# 68000.net
KiCad netlist of a schematic drawn in EAGLE
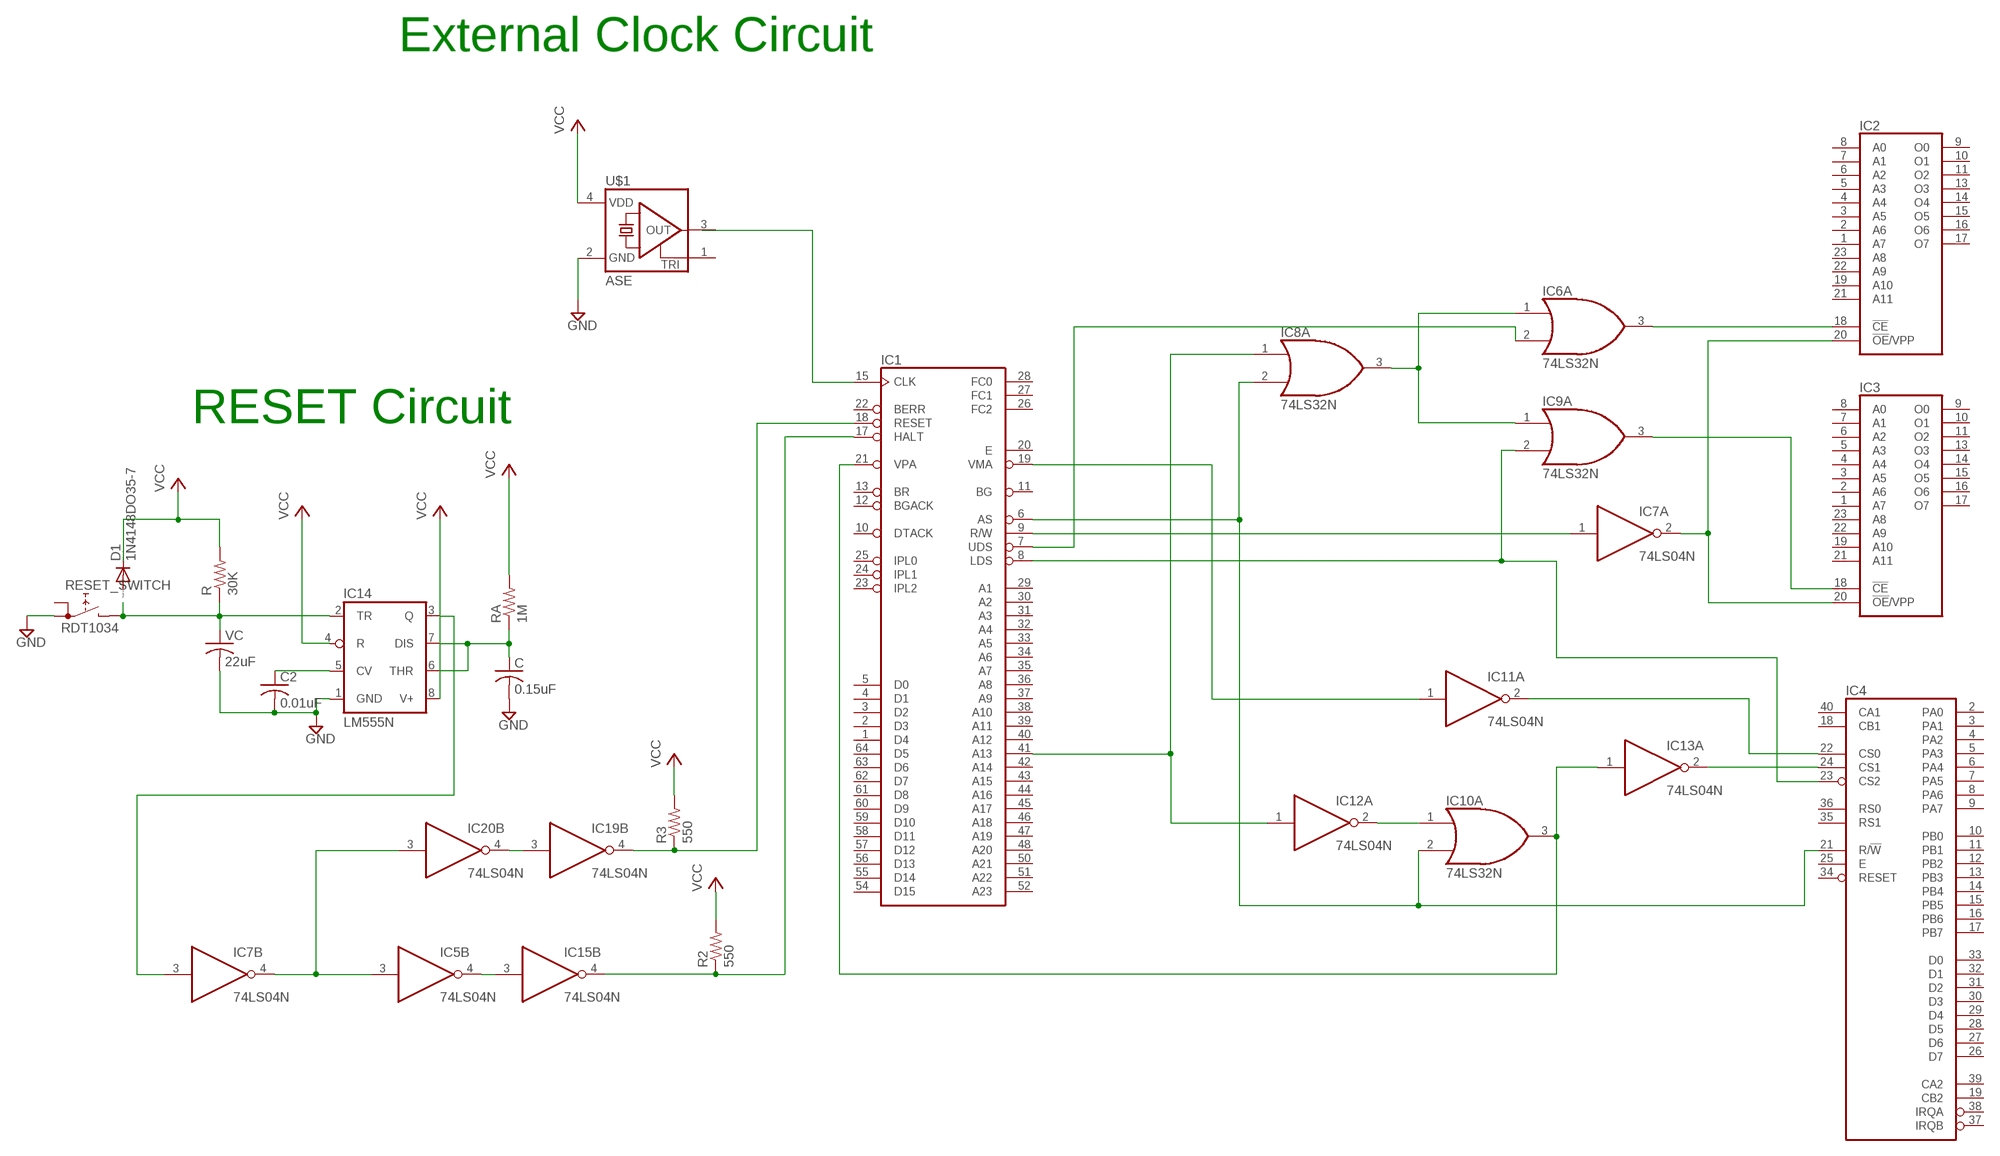
[diagram p0: schematic, sheet 1]

(export (version "E")
  (design (tool "Eeschema 10.0.6"))
  (components
    (comp (ref "C")
      (value "0.15uF")
      (footprint "eagle-import:C025-024X044")
      (libsource (lib "eagle-import") (part "C-US025-024X044"))
    )
    (comp (ref "C2")
      (value "0.01uF")
      (footprint "eagle-import:C025-024X044")
      (libsource (lib "eagle-import") (part "C-US025-024X044"))
    )
    (comp (ref "D1")
      (value "1N4148DO35-7")
      (footprint "eagle-import:DO35-7")
      (libsource (lib "eagle-import") (part "1N4148DO35-7"))
    )
    (comp (ref "IC1")
      (value "MC68000P")
      (footprint "eagle-import:DIL64")
      (libsource (lib "eagle-import") (part "MC68000P"))
    )
    (comp (ref "IC2")
      (value "2732")
      (footprint "eagle-import:DIL24")
      (libsource (lib "eagle-import") (part "2732"))
    )
    (comp (ref "IC3")
      (value "2732")
      (footprint "eagle-import:DIL24")
      (libsource (lib "eagle-import") (part "2732"))
    )
    (comp (ref "IC4")
      (value "6821")
      (footprint "eagle-import:DIL40")
      (fields (field (name "MF") "NTE ELECTRONICS") (field (name "MPN") "NTE6821"))
      (libsource (lib "eagle-import") (part "6821"))
    )
    (comp (ref "IC5")
      (value "74LS04N")
      (footprint "eagle-import:DIL14")
      (libsource (lib "eagle-import") (part "7404NLS"))
    )
    (comp (ref "IC6")
      (value "74LS32N")
      (footprint "eagle-import:DIL14")
      (libsource (lib "eagle-import") (part "7432NLS"))
    )
    (comp (ref "IC7")
      (value "74LS04N")
      (footprint "eagle-import:DIL14")
      (libsource (lib "eagle-import") (part "7404NLS"))
    )
    (comp (ref "IC8")
      (value "74LS32N")
      (footprint "eagle-import:DIL14")
      (libsource (lib "eagle-import") (part "7432NLS"))
    )
    (comp (ref "IC9")
      (value "74LS32N")
      (footprint "eagle-import:DIL14")
      (libsource (lib "eagle-import") (part "7432NLS"))
    )
    (comp (ref "IC10")
      (value "74LS32N")
      (footprint "eagle-import:DIL14")
      (libsource (lib "eagle-import") (part "7432NLS"))
    )
    (comp (ref "IC11")
      (value "74LS04N")
      (footprint "eagle-import:DIL14")
      (libsource (lib "eagle-import") (part "7404NLS"))
    )
    (comp (ref "IC12")
      (value "74LS04N")
      (footprint "eagle-import:DIL14")
      (libsource (lib "eagle-import") (part "7404NLS"))
    )
    (comp (ref "IC13")
      (value "74LS04N")
      (footprint "eagle-import:DIL14")
      (libsource (lib "eagle-import") (part "7404NLS"))
    )
    (comp (ref "IC14")
      (value "LM555N")
      (footprint "eagle-import:DIL08")
      (libsource (lib "eagle-import") (part "555NLM"))
    )
    (comp (ref "IC15")
      (value "74LS04N")
      (footprint "eagle-import:DIL14")
      (libsource (lib "eagle-import") (part "7404NLS"))
    )
    (comp (ref "IC19")
      (value "74LS04N")
      (footprint "eagle-import:DIL14")
      (libsource (lib "eagle-import") (part "7404NLS"))
    )
    (comp (ref "IC20")
      (value "74LS04N")
      (footprint "eagle-import:DIL14")
      (libsource (lib "eagle-import") (part "7404NLS"))
    )
    (comp (ref "R")
      (value "30K")
      (footprint "eagle-import:0204V")
      (libsource (lib "eagle-import") (part "R-US_0204/2V"))
    )
    (comp (ref "R2")
      (value "550")
      (footprint "eagle-import:0204V")
      (libsource (lib "eagle-import") (part "R-US_0204/2V"))
    )
    (comp (ref "R3")
      (value "550")
      (footprint "eagle-import:0204V")
      (libsource (lib "eagle-import") (part "R-US_0204/2V"))
    )
    (comp (ref "RA")
      (value "1M")
      (footprint "eagle-import:0204V")
      (libsource (lib "eagle-import") (part "R-US_0204/2V"))
    )
    (comp (ref "RESET_SWITCH")
      (value "RDT1034")
      (footprint "eagle-import:RDT1034")
      (libsource (lib "eagle-import") (part "RDT1034"))
    )
    (comp (ref "U$1")
      (value "ASE")
      (footprint "eagle-import:ASE")
      (libsource (lib "eagle-import") (part "ASE"))
    )
    (comp (ref "VC")
      (value "22uF")
      (footprint "eagle-import:C025-024X044")
      (libsource (lib "eagle-import") (part "C-US025-024X044"))
    )
  )
  (nets
    (net (code "1") (name "GND") (class "Default")
      (node (ref "C") (pin "2") (pinfunction "2_2") (pintype "passive"))
      (node (ref "C2") (pin "2") (pinfunction "2_2") (pintype "passive"))
      (node (ref "IC14") (pin "1") (pinfunction "GND_1") (pintype "power_in"))
      (node (ref "RESET_SWITCH") (pin "A1") (pinfunction "A1_A1") (pintype "passive"))
      (node (ref "U$1") (pin "2") (pinfunction "GND_2") (pintype "power_in"))
      (node (ref "VC") (pin "2") (pinfunction "2_2") (pintype "passive"))
    )
    (net (code "2") (name "Net-(IC1A-LDS)") (class "Default")
      (node (ref "IC1") (pin "8") (pinfunction "LDS_8") (pintype "output"))
      (node (ref "IC4") (pin "23") (pinfunction "CS2_23") (pintype "input"))
      (node (ref "IC9") (pin "2") (pinfunction "I1_2") (pintype "input"))
    )
    (net (code "3") (name "Net-(IC1A-R{slash}W)") (class "Default")
      (node (ref "IC1") (pin "9") (pinfunction "R/W_9") (pintype "output"))
      (node (ref "IC7") (pin "1") (pinfunction "I_1") (pintype "input"))
    )
    (net (code "4") (name "Net-(IC1A-UDS)") (class "Default")
      (node (ref "IC1") (pin "7") (pinfunction "UDS_7") (pintype "output"))
      (node (ref "IC6") (pin "2") (pinfunction "I1_2") (pintype "input"))
    )
    (net (code "5") (name "Net-(IC2A-~{CE})") (class "Default")
      (node (ref "IC2") (pin "18") (pinfunction "~{CE}_18") (pintype "input"))
      (node (ref "IC6") (pin "3") (pinfunction "O_3") (pintype "output"))
    )
    (net (code "6") (name "Net-(IC2A-~{OE}{slash}VPP)") (class "Default")
      (node (ref "IC2") (pin "20") (pinfunction "~{OE}/VPP_20") (pintype "input"))
      (node (ref "IC3") (pin "20") (pinfunction "~{OE}/VPP_20") (pintype "input"))
      (node (ref "IC7") (pin "2") (pinfunction "O_2") (pintype "output"))
    )
    (net (code "7") (name "Net-(IC3A-~{CE})") (class "Default")
      (node (ref "IC3") (pin "18") (pinfunction "~{CE}_18") (pintype "input"))
      (node (ref "IC9") (pin "3") (pinfunction "O_3") (pintype "output"))
    )
    (net (code "8") (name "Net-(IC6A-I0)") (class "Default")
      (node (ref "IC6") (pin "1") (pinfunction "I0_1") (pintype "input"))
      (node (ref "IC8") (pin "3") (pinfunction "O_3") (pintype "output"))
      (node (ref "IC9") (pin "1") (pinfunction "I0_1") (pintype "input"))
    )
    (net (code "9") (name "Net-(IC10A-I0)") (class "Default")
      (node (ref "IC10") (pin "1") (pinfunction "I0_1") (pintype "input"))
      (node (ref "IC12") (pin "2") (pinfunction "O_2") (pintype "output"))
    )
    (net (code "10") (name "Net-(IC10A-I1)") (class "Default")
      (node (ref "IC1") (pin "6") (pinfunction "AS_6") (pintype "output"))
      (node (ref "IC10") (pin "2") (pinfunction "I1_2") (pintype "input"))
      (node (ref "IC4") (pin "21") (pinfunction "R/~{W}_21") (pintype "input"))
      (node (ref "IC8") (pin "2") (pinfunction "I1_2") (pintype "input"))
    )
    (net (code "11") (name "Net-(IC10A-O)") (class "Default")
      (node (ref "IC1") (pin "21") (pinfunction "VPA_21") (pintype "input"))
      (node (ref "IC10") (pin "3") (pinfunction "O_3") (pintype "output"))
      (node (ref "IC13") (pin "1") (pinfunction "I_1") (pintype "input"))
    )
    (net (code "12") (name "Net-(IC11A-I)") (class "Default")
      (node (ref "IC1") (pin "19") (pinfunction "VMA_19") (pintype "output"))
      (node (ref "IC11") (pin "1") (pinfunction "I_1") (pintype "input"))
    )
    (net (code "13") (name "Net-(IC11A-O)") (class "Default")
      (node (ref "IC11") (pin "2") (pinfunction "O_2") (pintype "output"))
      (node (ref "IC4") (pin "22") (pinfunction "CS0_22") (pintype "input"))
    )
    (net (code "14") (name "Net-(IC12A-I)") (class "Default")
      (node (ref "IC1") (pin "41") (pinfunction "A13_41") (pintype "output"))
      (node (ref "IC12") (pin "1") (pinfunction "I_1") (pintype "input"))
      (node (ref "IC8") (pin "1") (pinfunction "I0_1") (pintype "input"))
    )
    (net (code "15") (name "Net-(IC13A-O)") (class "Default")
      (node (ref "IC13") (pin "2") (pinfunction "O_2") (pintype "output"))
      (node (ref "IC4") (pin "24") (pinfunction "CS1_24") (pintype "input"))
    )
    (net (code "16") (name "Net-(IC14-CV)") (class "Default")
      (node (ref "C2") (pin "1") (pinfunction "1_1") (pintype "passive"))
      (node (ref "IC14") (pin "5") (pinfunction "CV_5") (pintype "input"))
    )
    (net (code "17") (name "Net-(IC14-DIS)") (class "Default")
      (node (ref "C") (pin "1") (pinfunction "1_1") (pintype "passive"))
      (node (ref "IC14") (pin "6") (pinfunction "THR_6") (pintype "input"))
      (node (ref "IC14") (pin "7") (pinfunction "DIS_7") (pintype "input"))
      (node (ref "RA") (pin "1") (pinfunction "1_1") (pintype "passive"))
    )
    (net (code "18") (name "Net-(IC14-Q)") (class "Default")
      (node (ref "IC14") (pin "3") (pinfunction "Q_3") (pintype "output"))
      (node (ref "IC7") (pin "3") (pinfunction "I_3") (pintype "input"))
    )
    (net (code "19") (name "Net-(IC14-TR)") (class "Default")
      (node (ref "IC14") (pin "2") (pinfunction "TR_2") (pintype "input"))
      (node (ref "R") (pin "1") (pinfunction "1_1") (pintype "passive"))
      (node (ref "RESET_SWITCH") (pin "B") (pinfunction "B_B") (pintype "passive"))
      (node (ref "VC") (pin "1") (pinfunction "1_1") (pintype "passive"))
    )
    (net (code "20") (name "Net-(IC15B-I)") (class "Default")
      (node (ref "IC15") (pin "3") (pinfunction "I_3") (pintype "input"))
      (node (ref "IC5") (pin "4") (pinfunction "O_4") (pintype "output"))
    )
    (net (code "21") (name "Net-(IC15B-O)") (class "Default")
      (node (ref "IC1") (pin "17") (pinfunction "HALT_17") (pintype "bidirectional"))
      (node (ref "IC15") (pin "4") (pinfunction "O_4") (pintype "output"))
      (node (ref "R2") (pin "1") (pinfunction "1_1") (pintype "passive"))
    )
    (net (code "22") (name "Net-(IC19B-I)") (class "Default")
      (node (ref "IC19") (pin "3") (pinfunction "I_3") (pintype "input"))
      (node (ref "IC20") (pin "4") (pinfunction "O_4") (pintype "output"))
    )
    (net (code "23") (name "Net-(IC19B-O)") (class "Default")
      (node (ref "IC1") (pin "18") (pinfunction "RESET_18") (pintype "bidirectional"))
      (node (ref "IC19") (pin "4") (pinfunction "O_4") (pintype "output"))
      (node (ref "R3") (pin "1") (pinfunction "1_1") (pintype "passive"))
    )
    (net (code "24") (name "Net-(IC20B-I)") (class "Default")
      (node (ref "IC20") (pin "3") (pinfunction "I_3") (pintype "input"))
      (node (ref "IC5") (pin "3") (pinfunction "I_3") (pintype "input"))
      (node (ref "IC7") (pin "4") (pinfunction "O_4") (pintype "output"))
    )
    (net (code "25") (name "VCC") (class "Default")
      (node (ref "D1") (pin "C") (pinfunction "C_C") (pintype "passive"))
      (node (ref "IC14") (pin "4") (pinfunction "R_4") (pintype "input"))
      (node (ref "IC14") (pin "8") (pinfunction "V+_8") (pintype "power_in"))
      (node (ref "R") (pin "2") (pinfunction "2_2") (pintype "passive"))
      (node (ref "R2") (pin "2") (pinfunction "2_2") (pintype "passive"))
      (node (ref "R3") (pin "2") (pinfunction "2_2") (pintype "passive"))
      (node (ref "RA") (pin "2") (pinfunction "2_2") (pintype "passive"))
      (node (ref "U$1") (pin "4") (pinfunction "VDD_4") (pintype "power_in"))
    )
    (net (code "26") (name "unconnected-(D1-PadA)") (class "Default")
      (node (ref "D1") (pin "A") (pinfunction "A_A") (pintype "passive"))
    )
    (net (code "27") (name "unconnected-(IC1A-A1-Pad29)") (class "Default")
      (node (ref "IC1") (pin "29") (pinfunction "A1_29") (pintype "output"))
    )
    (net (code "28") (name "unconnected-(IC1A-A2-Pad30)") (class "Default")
      (node (ref "IC1") (pin "30") (pinfunction "A2_30") (pintype "output"))
    )
    (net (code "29") (name "unconnected-(IC1A-A3-Pad31)") (class "Default")
      (node (ref "IC1") (pin "31") (pinfunction "A3_31") (pintype "output"))
    )
    (net (code "30") (name "unconnected-(IC1A-A4-Pad32)") (class "Default")
      (node (ref "IC1") (pin "32") (pinfunction "A4_32") (pintype "output"))
    )
    (net (code "31") (name "unconnected-(IC1A-A5-Pad33)") (class "Default")
      (node (ref "IC1") (pin "33") (pinfunction "A5_33") (pintype "output"))
    )
    (net (code "32") (name "unconnected-(IC1A-A6-Pad34)") (class "Default")
      (node (ref "IC1") (pin "34") (pinfunction "A6_34") (pintype "output"))
    )
    (net (code "33") (name "unconnected-(IC1A-A7-Pad35)") (class "Default")
      (node (ref "IC1") (pin "35") (pinfunction "A7_35") (pintype "output"))
    )
    (net (code "34") (name "unconnected-(IC1A-A8-Pad36)") (class "Default")
      (node (ref "IC1") (pin "36") (pinfunction "A8_36") (pintype "output"))
    )
    (net (code "35") (name "unconnected-(IC1A-A9-Pad37)") (class "Default")
      (node (ref "IC1") (pin "37") (pinfunction "A9_37") (pintype "output"))
    )
    (net (code "36") (name "unconnected-(IC1A-A10-Pad38)") (class "Default")
      (node (ref "IC1") (pin "38") (pinfunction "A10_38") (pintype "output"))
    )
    (net (code "37") (name "unconnected-(IC1A-A11-Pad39)") (class "Default")
      (node (ref "IC1") (pin "39") (pinfunction "A11_39") (pintype "output"))
    )
    (net (code "38") (name "unconnected-(IC1A-A12-Pad40)") (class "Default")
      (node (ref "IC1") (pin "40") (pinfunction "A12_40") (pintype "output"))
    )
    (net (code "39") (name "unconnected-(IC1A-A14-Pad42)") (class "Default")
      (node (ref "IC1") (pin "42") (pinfunction "A14_42") (pintype "output"))
    )
    (net (code "40") (name "unconnected-(IC1A-A15-Pad43)") (class "Default")
      (node (ref "IC1") (pin "43") (pinfunction "A15_43") (pintype "output"))
    )
    (net (code "41") (name "unconnected-(IC1A-A16-Pad44)") (class "Default")
      (node (ref "IC1") (pin "44") (pinfunction "A16_44") (pintype "output"))
    )
    (net (code "42") (name "unconnected-(IC1A-A17-Pad45)") (class "Default")
      (node (ref "IC1") (pin "45") (pinfunction "A17_45") (pintype "output"))
    )
    (net (code "43") (name "unconnected-(IC1A-A18-Pad46)") (class "Default")
      (node (ref "IC1") (pin "46") (pinfunction "A18_46") (pintype "output"))
    )
    (net (code "44") (name "unconnected-(IC1A-A19-Pad47)") (class "Default")
      (node (ref "IC1") (pin "47") (pinfunction "A19_47") (pintype "output"))
    )
    (net (code "45") (name "unconnected-(IC1A-A20-Pad48)") (class "Default")
      (node (ref "IC1") (pin "48") (pinfunction "A20_48") (pintype "output"))
    )
    (net (code "46") (name "unconnected-(IC1A-A21-Pad50)") (class "Default")
      (node (ref "IC1") (pin "50") (pinfunction "A21_50") (pintype "output"))
    )
    (net (code "47") (name "unconnected-(IC1A-A22-Pad51)") (class "Default")
      (node (ref "IC1") (pin "51") (pinfunction "A22_51") (pintype "output"))
    )
    (net (code "48") (name "unconnected-(IC1A-A23-Pad52)") (class "Default")
      (node (ref "IC1") (pin "52") (pinfunction "A23_52") (pintype "output"))
    )
    (net (code "49") (name "unconnected-(IC1A-BERR-Pad22)") (class "Default")
      (node (ref "IC1") (pin "22") (pinfunction "BERR_22") (pintype "input"))
    )
    (net (code "50") (name "unconnected-(IC1A-BG-Pad11)") (class "Default")
      (node (ref "IC1") (pin "11") (pinfunction "BG_11") (pintype "output"))
    )
    (net (code "51") (name "unconnected-(IC1A-BGACK-Pad12)") (class "Default")
      (node (ref "IC1") (pin "12") (pinfunction "BGACK_12") (pintype "input"))
    )
    (net (code "52") (name "unconnected-(IC1A-BR-Pad13)") (class "Default")
      (node (ref "IC1") (pin "13") (pinfunction "BR_13") (pintype "input"))
    )
    (net (code "53") (name "unconnected-(IC1A-CLK-Pad15)") (class "Default")
      (node (ref "IC1") (pin "15") (pinfunction "CLK_15") (pintype "input"))
    )
    (net (code "54") (name "unconnected-(IC1A-D0-Pad5)") (class "Default")
      (node (ref "IC1") (pin "5") (pinfunction "D0_5") (pintype "bidirectional"))
    )
    (net (code "55") (name "unconnected-(IC1A-D1-Pad4)") (class "Default")
      (node (ref "IC1") (pin "4") (pinfunction "D1_4") (pintype "bidirectional"))
    )
    (net (code "56") (name "unconnected-(IC1A-D2-Pad3)") (class "Default")
      (node (ref "IC1") (pin "3") (pinfunction "D2_3") (pintype "bidirectional"))
    )
    (net (code "57") (name "unconnected-(IC1A-D3-Pad2)") (class "Default")
      (node (ref "IC1") (pin "2") (pinfunction "D3_2") (pintype "bidirectional"))
    )
    (net (code "58") (name "unconnected-(IC1A-D4-Pad1)") (class "Default")
      (node (ref "IC1") (pin "1") (pinfunction "D4_1") (pintype "bidirectional"))
    )
    (net (code "59") (name "unconnected-(IC1A-D5-Pad64)") (class "Default")
      (node (ref "IC1") (pin "64") (pinfunction "D5_64") (pintype "bidirectional"))
    )
    (net (code "60") (name "unconnected-(IC1A-D6-Pad63)") (class "Default")
      (node (ref "IC1") (pin "63") (pinfunction "D6_63") (pintype "bidirectional"))
    )
    (net (code "61") (name "unconnected-(IC1A-D7-Pad62)") (class "Default")
      (node (ref "IC1") (pin "62") (pinfunction "D7_62") (pintype "bidirectional"))
    )
    (net (code "62") (name "unconnected-(IC1A-D8-Pad61)") (class "Default")
      (node (ref "IC1") (pin "61") (pinfunction "D8_61") (pintype "bidirectional"))
    )
    (net (code "63") (name "unconnected-(IC1A-D9-Pad60)") (class "Default")
      (node (ref "IC1") (pin "60") (pinfunction "D9_60") (pintype "bidirectional"))
    )
    (net (code "64") (name "unconnected-(IC1A-D10-Pad59)") (class "Default")
      (node (ref "IC1") (pin "59") (pinfunction "D10_59") (pintype "bidirectional"))
    )
    (net (code "65") (name "unconnected-(IC1A-D11-Pad58)") (class "Default")
      (node (ref "IC1") (pin "58") (pinfunction "D11_58") (pintype "bidirectional"))
    )
    (net (code "66") (name "unconnected-(IC1A-D12-Pad57)") (class "Default")
      (node (ref "IC1") (pin "57") (pinfunction "D12_57") (pintype "bidirectional"))
    )
    (net (code "67") (name "unconnected-(IC1A-D13-Pad56)") (class "Default")
      (node (ref "IC1") (pin "56") (pinfunction "D13_56") (pintype "bidirectional"))
    )
    (net (code "68") (name "unconnected-(IC1A-D14-Pad55)") (class "Default")
      (node (ref "IC1") (pin "55") (pinfunction "D14_55") (pintype "bidirectional"))
    )
    (net (code "69") (name "unconnected-(IC1A-D15-Pad54)") (class "Default")
      (node (ref "IC1") (pin "54") (pinfunction "D15_54") (pintype "bidirectional"))
    )
    (net (code "70") (name "unconnected-(IC1A-DTACK-Pad10)") (class "Default")
      (node (ref "IC1") (pin "10") (pinfunction "DTACK_10") (pintype "input"))
    )
    (net (code "71") (name "unconnected-(IC1A-E-Pad20)") (class "Default")
      (node (ref "IC1") (pin "20") (pinfunction "E_20") (pintype "output"))
    )
    (net (code "72") (name "unconnected-(IC1A-FC0-Pad28)") (class "Default")
      (node (ref "IC1") (pin "28") (pinfunction "FC0_28") (pintype "output"))
    )
    (net (code "73") (name "unconnected-(IC1A-FC1-Pad27)") (class "Default")
      (node (ref "IC1") (pin "27") (pinfunction "FC1_27") (pintype "output"))
    )
    (net (code "74") (name "unconnected-(IC1A-FC2-Pad26)") (class "Default")
      (node (ref "IC1") (pin "26") (pinfunction "FC2_26") (pintype "output"))
    )
    (net (code "75") (name "unconnected-(IC1A-IPL0-Pad25)") (class "Default")
      (node (ref "IC1") (pin "25") (pinfunction "IPL0_25") (pintype "input"))
    )
    (net (code "76") (name "unconnected-(IC1A-IPL1-Pad24)") (class "Default")
      (node (ref "IC1") (pin "24") (pinfunction "IPL1_24") (pintype "input"))
    )
    (net (code "77") (name "unconnected-(IC1A-IPL2-Pad23)") (class "Default")
      (node (ref "IC1") (pin "23") (pinfunction "IPL2_23") (pintype "input"))
    )
    (net (code "78") (name "unconnected-(IC2A-A0-Pad8)") (class "Default")
      (node (ref "IC2") (pin "8") (pinfunction "A0_8") (pintype "input"))
    )
    (net (code "79") (name "unconnected-(IC2A-A1-Pad7)") (class "Default")
      (node (ref "IC2") (pin "7") (pinfunction "A1_7") (pintype "input"))
    )
    (net (code "80") (name "unconnected-(IC2A-A2-Pad6)") (class "Default")
      (node (ref "IC2") (pin "6") (pinfunction "A2_6") (pintype "input"))
    )
    (net (code "81") (name "unconnected-(IC2A-A3-Pad5)") (class "Default")
      (node (ref "IC2") (pin "5") (pinfunction "A3_5") (pintype "input"))
    )
    (net (code "82") (name "unconnected-(IC2A-A4-Pad4)") (class "Default")
      (node (ref "IC2") (pin "4") (pinfunction "A4_4") (pintype "input"))
    )
    (net (code "83") (name "unconnected-(IC2A-A5-Pad3)") (class "Default")
      (node (ref "IC2") (pin "3") (pinfunction "A5_3") (pintype "input"))
    )
    (net (code "84") (name "unconnected-(IC2A-A6-Pad2)") (class "Default")
      (node (ref "IC2") (pin "2") (pinfunction "A6_2") (pintype "input"))
    )
    (net (code "85") (name "unconnected-(IC2A-A7-Pad1)") (class "Default")
      (node (ref "IC2") (pin "1") (pinfunction "A7_1") (pintype "input"))
    )
    (net (code "86") (name "unconnected-(IC2A-A8-Pad23)") (class "Default")
      (node (ref "IC2") (pin "23") (pinfunction "A8_23") (pintype "input"))
    )
    (net (code "87") (name "unconnected-(IC2A-A9-Pad22)") (class "Default")
      (node (ref "IC2") (pin "22") (pinfunction "A9_22") (pintype "input"))
    )
    (net (code "88") (name "unconnected-(IC2A-A10-Pad19)") (class "Default")
      (node (ref "IC2") (pin "19") (pinfunction "A10_19") (pintype "input"))
    )
    (net (code "89") (name "unconnected-(IC2A-A11-Pad21)") (class "Default")
      (node (ref "IC2") (pin "21") (pinfunction "A11_21") (pintype "input"))
    )
    (net (code "90") (name "unconnected-(IC2A-O0-Pad9)") (class "Default")
      (node (ref "IC2") (pin "9") (pinfunction "O0_9") (pintype "tri_state"))
    )
    (net (code "91") (name "unconnected-(IC2A-O1-Pad10)") (class "Default")
      (node (ref "IC2") (pin "10") (pinfunction "O1_10") (pintype "tri_state"))
    )
    (net (code "92") (name "unconnected-(IC2A-O2-Pad11)") (class "Default")
      (node (ref "IC2") (pin "11") (pinfunction "O2_11") (pintype "tri_state"))
    )
    (net (code "93") (name "unconnected-(IC2A-O3-Pad13)") (class "Default")
      (node (ref "IC2") (pin "13") (pinfunction "O3_13") (pintype "tri_state"))
    )
    (net (code "94") (name "unconnected-(IC2A-O4-Pad14)") (class "Default")
      (node (ref "IC2") (pin "14") (pinfunction "O4_14") (pintype "tri_state"))
    )
    (net (code "95") (name "unconnected-(IC2A-O5-Pad15)") (class "Default")
      (node (ref "IC2") (pin "15") (pinfunction "O5_15") (pintype "tri_state"))
    )
    (net (code "96") (name "unconnected-(IC2A-O6-Pad16)") (class "Default")
      (node (ref "IC2") (pin "16") (pinfunction "O6_16") (pintype "tri_state"))
    )
    (net (code "97") (name "unconnected-(IC2A-O7-Pad17)") (class "Default")
      (node (ref "IC2") (pin "17") (pinfunction "O7_17") (pintype "tri_state"))
    )
    (net (code "98") (name "unconnected-(IC3A-A0-Pad8)") (class "Default")
      (node (ref "IC3") (pin "8") (pinfunction "A0_8") (pintype "input"))
    )
    (net (code "99") (name "unconnected-(IC3A-A1-Pad7)") (class "Default")
      (node (ref "IC3") (pin "7") (pinfunction "A1_7") (pintype "input"))
    )
    (net (code "100") (name "unconnected-(IC3A-A2-Pad6)") (class "Default")
      (node (ref "IC3") (pin "6") (pinfunction "A2_6") (pintype "input"))
    )
    (net (code "101") (name "unconnected-(IC3A-A3-Pad5)") (class "Default")
      (node (ref "IC3") (pin "5") (pinfunction "A3_5") (pintype "input"))
    )
    (net (code "102") (name "unconnected-(IC3A-A4-Pad4)") (class "Default")
      (node (ref "IC3") (pin "4") (pinfunction "A4_4") (pintype "input"))
    )
    (net (code "103") (name "unconnected-(IC3A-A5-Pad3)") (class "Default")
      (node (ref "IC3") (pin "3") (pinfunction "A5_3") (pintype "input"))
    )
    (net (code "104") (name "unconnected-(IC3A-A6-Pad2)") (class "Default")
      (node (ref "IC3") (pin "2") (pinfunction "A6_2") (pintype "input"))
    )
    (net (code "105") (name "unconnected-(IC3A-A7-Pad1)") (class "Default")
      (node (ref "IC3") (pin "1") (pinfunction "A7_1") (pintype "input"))
    )
    (net (code "106") (name "unconnected-(IC3A-A8-Pad23)") (class "Default")
      (node (ref "IC3") (pin "23") (pinfunction "A8_23") (pintype "input"))
    )
    (net (code "107") (name "unconnected-(IC3A-A9-Pad22)") (class "Default")
      (node (ref "IC3") (pin "22") (pinfunction "A9_22") (pintype "input"))
    )
    (net (code "108") (name "unconnected-(IC3A-A10-Pad19)") (class "Default")
      (node (ref "IC3") (pin "19") (pinfunction "A10_19") (pintype "input"))
    )
    (net (code "109") (name "unconnected-(IC3A-A11-Pad21)") (class "Default")
      (node (ref "IC3") (pin "21") (pinfunction "A11_21") (pintype "input"))
    )
    (net (code "110") (name "unconnected-(IC3A-O0-Pad9)") (class "Default")
      (node (ref "IC3") (pin "9") (pinfunction "O0_9") (pintype "tri_state"))
    )
    (net (code "111") (name "unconnected-(IC3A-O1-Pad10)") (class "Default")
      (node (ref "IC3") (pin "10") (pinfunction "O1_10") (pintype "tri_state"))
    )
    (net (code "112") (name "unconnected-(IC3A-O2-Pad11)") (class "Default")
      (node (ref "IC3") (pin "11") (pinfunction "O2_11") (pintype "tri_state"))
    )
    (net (code "113") (name "unconnected-(IC3A-O3-Pad13)") (class "Default")
      (node (ref "IC3") (pin "13") (pinfunction "O3_13") (pintype "tri_state"))
    )
    (net (code "114") (name "unconnected-(IC3A-O4-Pad14)") (class "Default")
      (node (ref "IC3") (pin "14") (pinfunction "O4_14") (pintype "tri_state"))
    )
    (net (code "115") (name "unconnected-(IC3A-O5-Pad15)") (class "Default")
      (node (ref "IC3") (pin "15") (pinfunction "O5_15") (pintype "tri_state"))
    )
    (net (code "116") (name "unconnected-(IC3A-O6-Pad16)") (class "Default")
      (node (ref "IC3") (pin "16") (pinfunction "O6_16") (pintype "tri_state"))
    )
    (net (code "117") (name "unconnected-(IC3A-O7-Pad17)") (class "Default")
      (node (ref "IC3") (pin "17") (pinfunction "O7_17") (pintype "tri_state"))
    )
    (net (code "118") (name "unconnected-(IC4A-CA1-Pad40)") (class "Default")
      (node (ref "IC4") (pin "40") (pinfunction "CA1_40") (pintype "input"))
    )
    (net (code "119") (name "unconnected-(IC4A-CA2-Pad39)") (class "Default")
      (node (ref "IC4") (pin "39") (pinfunction "CA2_39") (pintype "bidirectional"))
    )
    (net (code "120") (name "unconnected-(IC4A-CB1-Pad18)") (class "Default")
      (node (ref "IC4") (pin "18") (pinfunction "CB1_18") (pintype "input"))
    )
    (net (code "121") (name "unconnected-(IC4A-CB2-Pad19)") (class "Default")
      (node (ref "IC4") (pin "19") (pinfunction "CB2_19") (pintype "bidirectional"))
    )
    (net (code "122") (name "unconnected-(IC4A-D0-Pad33)") (class "Default")
      (node (ref "IC4") (pin "33") (pinfunction "D0_33") (pintype "bidirectional"))
    )
    (net (code "123") (name "unconnected-(IC4A-D1-Pad32)") (class "Default")
      (node (ref "IC4") (pin "32") (pinfunction "D1_32") (pintype "bidirectional"))
    )
    (net (code "124") (name "unconnected-(IC4A-D2-Pad31)") (class "Default")
      (node (ref "IC4") (pin "31") (pinfunction "D2_31") (pintype "bidirectional"))
    )
    (net (code "125") (name "unconnected-(IC4A-D3-Pad30)") (class "Default")
      (node (ref "IC4") (pin "30") (pinfunction "D3_30") (pintype "bidirectional"))
    )
    (net (code "126") (name "unconnected-(IC4A-D4-Pad29)") (class "Default")
      (node (ref "IC4") (pin "29") (pinfunction "D4_29") (pintype "bidirectional"))
    )
    (net (code "127") (name "unconnected-(IC4A-D5-Pad28)") (class "Default")
      (node (ref "IC4") (pin "28") (pinfunction "D5_28") (pintype "bidirectional"))
    )
    (net (code "128") (name "unconnected-(IC4A-D6-Pad27)") (class "Default")
      (node (ref "IC4") (pin "27") (pinfunction "D6_27") (pintype "bidirectional"))
    )
    (net (code "129") (name "unconnected-(IC4A-D7-Pad26)") (class "Default")
      (node (ref "IC4") (pin "26") (pinfunction "D7_26") (pintype "bidirectional"))
    )
    (net (code "130") (name "unconnected-(IC4A-E-Pad25)") (class "Default")
      (node (ref "IC4") (pin "25") (pinfunction "E_25") (pintype "input"))
    )
    (net (code "131") (name "unconnected-(IC4A-IRQA-Pad38)") (class "Default")
      (node (ref "IC4") (pin "38") (pinfunction "IRQA_38") (pintype "open_collector"))
    )
    (net (code "132") (name "unconnected-(IC4A-IRQB-Pad37)") (class "Default")
      (node (ref "IC4") (pin "37") (pinfunction "IRQB_37") (pintype "open_collector"))
    )
    (net (code "133") (name "unconnected-(IC4A-PA0-Pad2)") (class "Default")
      (node (ref "IC4") (pin "2") (pinfunction "PA0_2") (pintype "bidirectional"))
    )
    (net (code "134") (name "unconnected-(IC4A-PA1-Pad3)") (class "Default")
      (node (ref "IC4") (pin "3") (pinfunction "PA1_3") (pintype "bidirectional"))
    )
    (net (code "135") (name "unconnected-(IC4A-PA2-Pad4)") (class "Default")
      (node (ref "IC4") (pin "4") (pinfunction "PA2_4") (pintype "bidirectional"))
    )
    (net (code "136") (name "unconnected-(IC4A-PA3-Pad5)") (class "Default")
      (node (ref "IC4") (pin "5") (pinfunction "PA3_5") (pintype "bidirectional"))
    )
    (net (code "137") (name "unconnected-(IC4A-PA4-Pad6)") (class "Default")
      (node (ref "IC4") (pin "6") (pinfunction "PA4_6") (pintype "bidirectional"))
    )
    (net (code "138") (name "unconnected-(IC4A-PA5-Pad7)") (class "Default")
      (node (ref "IC4") (pin "7") (pinfunction "PA5_7") (pintype "bidirectional"))
    )
    (net (code "139") (name "unconnected-(IC4A-PA6-Pad8)") (class "Default")
      (node (ref "IC4") (pin "8") (pinfunction "PA6_8") (pintype "bidirectional"))
    )
    (net (code "140") (name "unconnected-(IC4A-PA7-Pad9)") (class "Default")
      (node (ref "IC4") (pin "9") (pinfunction "PA7_9") (pintype "bidirectional"))
    )
    (net (code "141") (name "unconnected-(IC4A-PB0-Pad10)") (class "Default")
      (node (ref "IC4") (pin "10") (pinfunction "PB0_10") (pintype "bidirectional"))
    )
    (net (code "142") (name "unconnected-(IC4A-PB1-Pad11)") (class "Default")
      (node (ref "IC4") (pin "11") (pinfunction "PB1_11") (pintype "bidirectional"))
    )
    (net (code "143") (name "unconnected-(IC4A-PB2-Pad12)") (class "Default")
      (node (ref "IC4") (pin "12") (pinfunction "PB2_12") (pintype "bidirectional"))
    )
    (net (code "144") (name "unconnected-(IC4A-PB3-Pad13)") (class "Default")
      (node (ref "IC4") (pin "13") (pinfunction "PB3_13") (pintype "bidirectional"))
    )
    (net (code "145") (name "unconnected-(IC4A-PB4-Pad14)") (class "Default")
      (node (ref "IC4") (pin "14") (pinfunction "PB4_14") (pintype "bidirectional"))
    )
    (net (code "146") (name "unconnected-(IC4A-PB5-Pad15)") (class "Default")
      (node (ref "IC4") (pin "15") (pinfunction "PB5_15") (pintype "bidirectional"))
    )
    (net (code "147") (name "unconnected-(IC4A-PB6-Pad16)") (class "Default")
      (node (ref "IC4") (pin "16") (pinfunction "PB6_16") (pintype "bidirectional"))
    )
    (net (code "148") (name "unconnected-(IC4A-PB7-Pad17)") (class "Default")
      (node (ref "IC4") (pin "17") (pinfunction "PB7_17") (pintype "bidirectional"))
    )
    (net (code "149") (name "unconnected-(IC4A-RESET-Pad34)") (class "Default")
      (node (ref "IC4") (pin "34") (pinfunction "RESET_34") (pintype "input"))
    )
    (net (code "150") (name "unconnected-(IC4A-RS0-Pad36)") (class "Default")
      (node (ref "IC4") (pin "36") (pinfunction "RS0_36") (pintype "input"))
    )
    (net (code "151") (name "unconnected-(IC4A-RS1-Pad35)") (class "Default")
      (node (ref "IC4") (pin "35") (pinfunction "RS1_35") (pintype "input"))
    )
    (net (code "152") (name "unconnected-(RESET_SWITCH-PadA)") (class "Default")
      (node (ref "RESET_SWITCH") (pin "A") (pinfunction "A_A") (pintype "passive"))
    )
    (net (code "153") (name "unconnected-(U$1-OUT-Pad3)") (class "Default")
      (node (ref "U$1") (pin "3") (pinfunction "OUT_3") (pintype "output"))
    )
    (net (code "154") (name "unconnected-(U$1-TRI-Pad1)") (class "Default")
      (node (ref "U$1") (pin "1") (pinfunction "TRI_1") (pintype "input"))
    )
  )
)
